# TPT02rrrrr.net
KiCad netlist of a schematic drawn in EAGLE
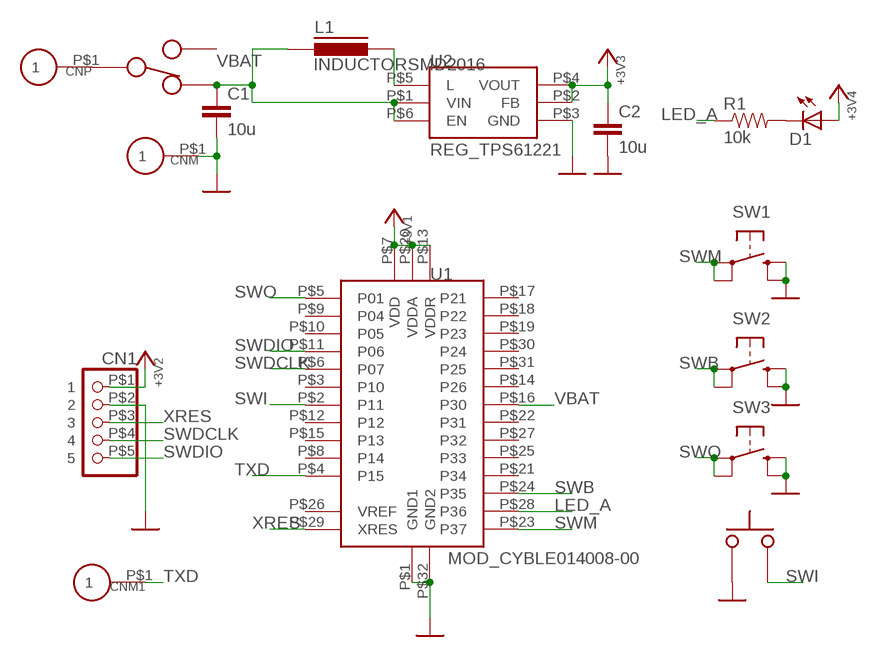
[diagram p0: schematic, sheet 1]

(export (version "E")
  (design (tool "Eeschema 10.0.6"))
  (components
    (comp (ref "C1")
      (value "10u")
      (footprint "eagle-import:0603")
      (libsource (lib "eagle-import") (part "CAP0603"))
    )
    (comp (ref "C2")
      (value "10u")
      (footprint "eagle-import:0603")
      (libsource (lib "eagle-import") (part "CAP0603"))
    )
    (comp (ref "CN1")
      (value "CON_PINHD-1X550MIL")
      (footprint "eagle-import:1X5_50MIL")
      (libsource (lib "eagle-import") (part "CON_PINHD-1X550MIL"))
    )
    (comp (ref "CNM")
      (value "CON_P01SMD1MM")
      (footprint "eagle-import:PAD_SMD1MM")
      (libsource (lib "eagle-import") (part "CON_P01SMD1MM"))
    )
    (comp (ref "CNM1")
      (value "CON_P01SMD1MM")
      (footprint "eagle-import:PAD_SMD1MM")
      (libsource (lib "eagle-import") (part "CON_P01SMD1MM"))
    )
    (comp (ref "CNP")
      (value "CON_P01SMD1MM")
      (footprint "eagle-import:PAD_SMD1MM")
      (libsource (lib "eagle-import") (part "CON_P01SMD1MM"))
    )
    (comp (ref "D1")
      (value "LED0603")
      (footprint "eagle-import:SPARKFUN_LED-0603")
      (libsource (lib "eagle-import") (part "LED0603"))
    )
    (comp (ref "L1")
      (value "INDUCTORSMD2016")
      (footprint "eagle-import:2016")
      (libsource (lib "eagle-import") (part "INDUCTORSMD2016"))
    )
    (comp (ref "R1")
      (value "10k")
      (footprint "eagle-import:0603")
      (libsource (lib "eagle-import") (part "RES0603"))
    )
    (comp (ref "SW1")
      (value "SW_TACTEVQP2")
      (footprint "eagle-import:SW_EVQP2")
      (libsource (lib "eagle-import") (part "SW_TACTEVQP2"))
    )
    (comp (ref "SW2")
      (value "SW_TACTEVQPLNA08NOGND")
      (footprint "eagle-import:SW_EVQPLBA08_NOGND")
      (libsource (lib "eagle-import") (part "SW_TACTEVQPLNA08NOGND"))
    )
    (comp (ref "SW3")
      (value "SW_TACTEVQPLNA08NOGND")
      (footprint "eagle-import:SW_EVQPLBA08_NOGND")
      (libsource (lib "eagle-import") (part "SW_TACTEVQPLNA08NOGND"))
    )
    (comp (ref "SW4")
      (value "SW_SLIDECUS12B")
      (footprint "eagle-import:SW_CUS-12B")
      (libsource (lib "eagle-import") (part "SW_SLIDECUS12B"))
    )
    (comp (ref "SW5")
      (value "SW_TACT2PB3U3000")
      (footprint "eagle-import:SW_B3U-3000P")
      (libsource (lib "eagle-import") (part "SW_TACT2PB3U3000"))
    )
    (comp (ref "U1")
      (value "MOD_CYBLE014008-00")
      (footprint "eagle-import:MOD_CYBLE014008-00")
      (libsource (lib "eagle-import") (part "MOD_CYBLE014008-00"))
    )
    (comp (ref "U2")
      (value "REG_TPS61221")
      (footprint "eagle-import:SC70-6")
      (libsource (lib "eagle-import") (part "REG_TPS61221"))
    )
  )
  (nets
    (net (code "1") (name "/LED_A") (class "Default")
      (node (ref "R1") (pin "1") (pinfunction "1_1") (pintype "passive"))
      (node (ref "U1") (pin "P$28") (pinfunction "P36_P$28") (pintype "bidirectional"))
    )
    (net (code "2") (name "/P$3") (class "Default")
      (node (ref "SW4") (pin "P$3") (pinfunction "P$3_P$3") (pintype "power_in"))
    )
    (net (code "3") (name "/SWB") (class "Default")
      (node (ref "SW2") (pin "A1") (pinfunction "P_A1") (pintype "passive"))
      (node (ref "SW2") (pin "A2") (pinfunction "P1_A2") (pintype "passive"))
      (node (ref "U1") (pin "P$24") (pinfunction "P35_P$24") (pintype "bidirectional"))
    )
    (net (code "4") (name "/SWDCLK") (class "Default")
      (node (ref "CN1") (pin "P$4") (pinfunction "4_P$4") (pintype "passive"))
      (node (ref "U1") (pin "P$6") (pinfunction "P07_P$6") (pintype "bidirectional"))
    )
    (net (code "5") (name "/SWDIO") (class "Default")
      (node (ref "CN1") (pin "P$5") (pinfunction "5_P$5") (pintype "passive"))
      (node (ref "U1") (pin "P$11") (pinfunction "P06_P$11") (pintype "bidirectional"))
    )
    (net (code "6") (name "/SWI") (class "Default")
      (node (ref "SW5") (pin "P$1") (pinfunction "P$1_P$1") (pintype "passive"))
      (node (ref "U1") (pin "P$2") (pinfunction "P11_P$2") (pintype "bidirectional"))
    )
    (net (code "7") (name "/SWM") (class "Default")
      (node (ref "SW1") (pin "PA1") (pinfunction "P_PA1") (pintype "passive"))
      (node (ref "SW1") (pin "PA2") (pinfunction "P1_PA2") (pintype "passive"))
      (node (ref "U1") (pin "P$23") (pinfunction "P37_P$23") (pintype "bidirectional"))
    )
    (net (code "8") (name "/SWO") (class "Default")
      (node (ref "SW3") (pin "A1") (pinfunction "P_A1") (pintype "passive"))
      (node (ref "SW3") (pin "A2") (pinfunction "P1_A2") (pintype "passive"))
      (node (ref "U1") (pin "P$5") (pinfunction "P01_P$5") (pintype "bidirectional"))
    )
    (net (code "9") (name "/TXD") (class "Default")
      (node (ref "CNM1") (pin "P$1") (pinfunction "1_P$1") (pintype "bidirectional"))
      (node (ref "U1") (pin "P$4") (pinfunction "P15_P$4") (pintype "bidirectional"))
    )
    (net (code "10") (name "/VBAT") (class "Default")
      (node (ref "C1") (pin "1") (pinfunction "1_1") (pintype "passive"))
      (node (ref "L1") (pin "P$1") (pinfunction "1_P$1") (pintype "passive"))
      (node (ref "SW4") (pin "P$1") (pinfunction "P$1_P$1") (pintype "power_in"))
      (node (ref "U1") (pin "P$16") (pinfunction "P30_P$16") (pintype "bidirectional"))
      (node (ref "U2") (pin "P$1") (pinfunction "VIN_P$1") (pintype "bidirectional"))
      (node (ref "U2") (pin "P$6") (pinfunction "EN_P$6") (pintype "bidirectional"))
    )
    (net (code "11") (name "/XRES") (class "Default")
      (node (ref "CN1") (pin "P$3") (pinfunction "3_P$3") (pintype "passive"))
      (node (ref "U1") (pin "P$29") (pinfunction "XRES_P$29") (pintype "bidirectional"))
    )
    (net (code "12") (name "Net-(CNP-1)") (class "Default")
      (node (ref "CNP") (pin "P$1") (pinfunction "1_P$1") (pintype "bidirectional"))
      (node (ref "SW4") (pin "P$2") (pinfunction "P$2_P$2") (pintype "power_in"))
    )
    (net (code "13") (name "Net-(D1-PadC)") (class "Default")
      (node (ref "D1") (pin "C") (pinfunction "C_C") (pintype "passive"))
      (node (ref "R1") (pin "2") (pinfunction "2_2") (pintype "passive"))
    )
    (net (code "14") (name "Net-(L1-2)") (class "Default")
      (node (ref "L1") (pin "P$2") (pinfunction "2_P$2") (pintype "passive"))
      (node (ref "U2") (pin "P$5") (pinfunction "L_P$5") (pintype "bidirectional"))
    )
    (net (code "15") (name "POW_+3V3") (class "Default")
      (node (ref "C2") (pin "1") (pinfunction "1_1") (pintype "passive"))
      (node (ref "CN1") (pin "P$1") (pinfunction "1_P$1") (pintype "passive"))
      (node (ref "D1") (pin "A") (pinfunction "A_A") (pintype "passive"))
      (node (ref "U1") (pin "P$13") (pinfunction "VDDR_P$13") (pintype "bidirectional"))
      (node (ref "U1") (pin "P$20") (pinfunction "VDDA_P$20") (pintype "bidirectional"))
      (node (ref "U1") (pin "P$7") (pinfunction "VDD_P$7") (pintype "bidirectional"))
      (node (ref "U2") (pin "P$2") (pinfunction "FB_P$2") (pintype "bidirectional"))
      (node (ref "U2") (pin "P$4") (pinfunction "VOUT_P$4") (pintype "bidirectional"))
    )
    (net (code "16") (name "POW_GND") (class "Default")
      (node (ref "C1") (pin "2") (pinfunction "2_2") (pintype "passive"))
      (node (ref "C2") (pin "2") (pinfunction "2_2") (pintype "passive"))
      (node (ref "CN1") (pin "P$2") (pinfunction "2_P$2") (pintype "passive"))
      (node (ref "CNM") (pin "P$1") (pinfunction "1_P$1") (pintype "bidirectional"))
      (node (ref "SW1") (pin "PB1") (pinfunction "S_PB1") (pintype "passive"))
      (node (ref "SW1") (pin "PB2") (pinfunction "S1_PB2") (pintype "passive"))
      (node (ref "SW2") (pin "B1") (pinfunction "S_B1") (pintype "passive"))
      (node (ref "SW2") (pin "B2") (pinfunction "S1_B2") (pintype "passive"))
      (node (ref "SW3") (pin "B1") (pinfunction "S_B1") (pintype "passive"))
      (node (ref "SW3") (pin "B2") (pinfunction "S1_B2") (pintype "passive"))
      (node (ref "SW5") (pin "P$2") (pinfunction "P$2_P$2") (pintype "passive"))
      (node (ref "U1") (pin "P$1") (pinfunction "GND1_P$1") (pintype "bidirectional"))
      (node (ref "U1") (pin "P$32") (pinfunction "GND2_P$32") (pintype "bidirectional"))
      (node (ref "U2") (pin "P$3") (pinfunction "GND_P$3") (pintype "bidirectional"))
    )
    (net (code "17") (name "unconnected-(U1-P04-PadP$9)") (class "Default")
      (node (ref "U1") (pin "P$9") (pinfunction "P04_P$9") (pintype "bidirectional"))
    )
    (net (code "18") (name "unconnected-(U1-P05-PadP$10)") (class "Default")
      (node (ref "U1") (pin "P$10") (pinfunction "P05_P$10") (pintype "bidirectional"))
    )
    (net (code "19") (name "unconnected-(U1-P10-PadP$3)") (class "Default")
      (node (ref "U1") (pin "P$3") (pinfunction "P10_P$3") (pintype "bidirectional"))
    )
    (net (code "20") (name "unconnected-(U1-P12-PadP$12)") (class "Default")
      (node (ref "U1") (pin "P$12") (pinfunction "P12_P$12") (pintype "bidirectional"))
    )
    (net (code "21") (name "unconnected-(U1-P13-PadP$15)") (class "Default")
      (node (ref "U1") (pin "P$15") (pinfunction "P13_P$15") (pintype "bidirectional"))
    )
    (net (code "22") (name "unconnected-(U1-P14-PadP$8)") (class "Default")
      (node (ref "U1") (pin "P$8") (pinfunction "P14_P$8") (pintype "bidirectional"))
    )
    (net (code "23") (name "unconnected-(U1-P21-PadP$17)") (class "Default")
      (node (ref "U1") (pin "P$17") (pinfunction "P21_P$17") (pintype "bidirectional"))
    )
    (net (code "24") (name "unconnected-(U1-P22-PadP$18)") (class "Default")
      (node (ref "U1") (pin "P$18") (pinfunction "P22_P$18") (pintype "bidirectional"))
    )
    (net (code "25") (name "unconnected-(U1-P23-PadP$19)") (class "Default")
      (node (ref "U1") (pin "P$19") (pinfunction "P23_P$19") (pintype "bidirectional"))
    )
    (net (code "26") (name "unconnected-(U1-P24-PadP$30)") (class "Default")
      (node (ref "U1") (pin "P$30") (pinfunction "P24_P$30") (pintype "bidirectional"))
    )
    (net (code "27") (name "unconnected-(U1-P25-PadP$31)") (class "Default")
      (node (ref "U1") (pin "P$31") (pinfunction "P25_P$31") (pintype "bidirectional"))
    )
    (net (code "28") (name "unconnected-(U1-P26-PadP$14)") (class "Default")
      (node (ref "U1") (pin "P$14") (pinfunction "P26_P$14") (pintype "bidirectional"))
    )
    (net (code "29") (name "unconnected-(U1-P31-PadP$22)") (class "Default")
      (node (ref "U1") (pin "P$22") (pinfunction "P31_P$22") (pintype "bidirectional"))
    )
    (net (code "30") (name "unconnected-(U1-P32-PadP$27)") (class "Default")
      (node (ref "U1") (pin "P$27") (pinfunction "P32_P$27") (pintype "bidirectional"))
    )
    (net (code "31") (name "unconnected-(U1-P33-PadP$25)") (class "Default")
      (node (ref "U1") (pin "P$25") (pinfunction "P33_P$25") (pintype "bidirectional"))
    )
    (net (code "32") (name "unconnected-(U1-P34-PadP$21)") (class "Default")
      (node (ref "U1") (pin "P$21") (pinfunction "P34_P$21") (pintype "bidirectional"))
    )
    (net (code "33") (name "unconnected-(U1-VREF-PadP$26)") (class "Default")
      (node (ref "U1") (pin "P$26") (pinfunction "VREF_P$26") (pintype "bidirectional"))
    )
  )
)
